# 01_Powersupply.net
KiCad netlist of a schematic drawn in Altium Designer
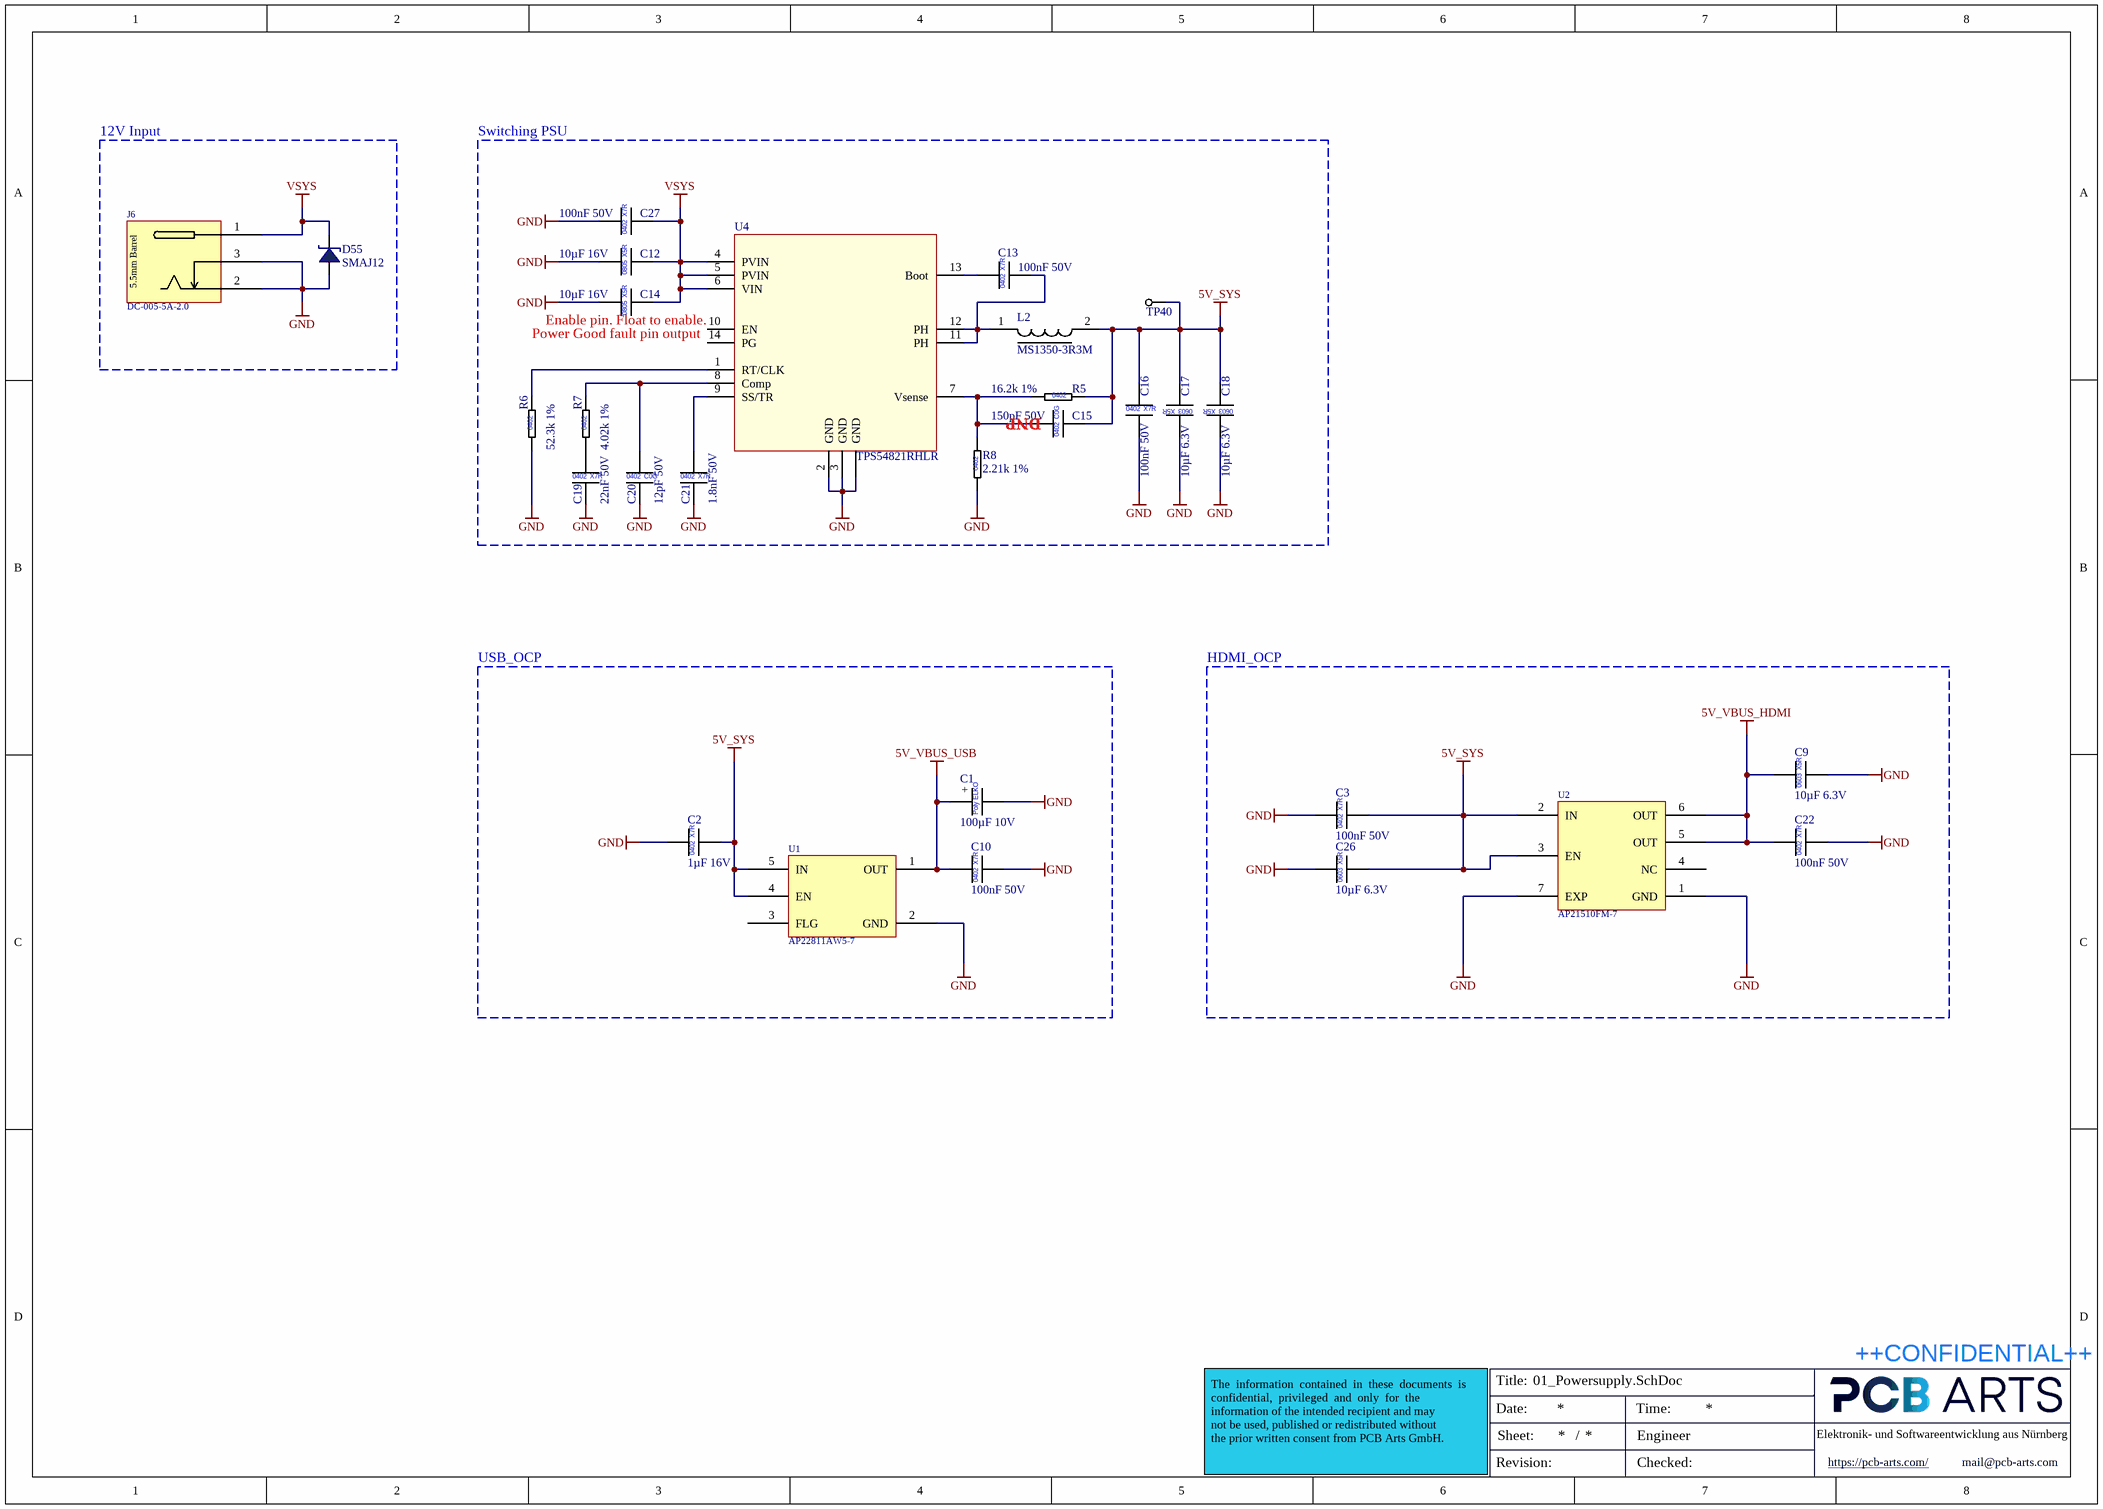
[diagram p0: 01_Powersupply.SchDoc]

(export (version "E")
  (design (tool "Eeschema 10.0.6"))
  (components
    (comp (ref "C1")
      (value "100µF 10V")
      (footprint "Cap:WCAP-ASLI_D5H5.5")
      (description "Organische Polymer-Aluminiumkondensatoren 100uF 10 Volts 20%")
      (libsource (lib "Cap") (part "CAP_D5L5.5_100µF_10V"))
    )
    (comp (ref "C2")
      (value "1µF 16V")
      (footprint "Cap:CAP_0402")
      (description "Multilayer Ceramic Capacitors MLCC - SMD/SMT 0402 16VDC")
      (libsource (lib "Cap") (part "CAP_0402_1µF_16V"))
    )
    (comp (ref "C3")
      (value "100nF 50V")
      (footprint "Cap:CAP_0402")
      (description "Multilayer Ceramic Capacitors MLCC - SMD/SMT 0402 50VDC")
      (libsource (lib "Cap") (part "CAP_0402_100nF_50V"))
    )
    (comp (ref "C9")
      (value "10µF 6.3V")
      (footprint "Cap:CAP_0603")
      (description "Multilayer Ceramic Capacitors MLCC - SMD/SMT 0603 6.3VDC")
      (libsource (lib "Cap") (part "CAP_0603_10µF_6.3V"))
    )
    (comp (ref "C10")
      (value "100nF 50V")
      (footprint "Cap:CAP_0402")
      (description "Multilayer Ceramic Capacitors MLCC - SMD/SMT 0402 50VDC")
      (libsource (lib "Cap") (part "CAP_0402_100nF_50V"))
    )
    (comp (ref "C12")
      (value "10µF 16V")
      (footprint "AlemNano 201029:CAP_0805")
      (description "Multilayer Ceramic Capacitors MLCC - SMD/SMT 0805 16VDC")
      (libsource (lib "AlemNano 201029") (part "CAP_0805_10µF_16V"))
    )
    (comp (ref "C13")
      (value "100nF 50V")
      (footprint "AlemNano 201029:CAP_0402")
      (description "Multilayer Ceramic Capacitors MLCC - SMD/SMT 0402 50VDC")
      (libsource (lib "AlemNano 201029") (part "CAP_0402_100nF_50V"))
    )
    (comp (ref "C14")
      (value "10µF 16V")
      (footprint "AlemNano 201029:CAP_0805")
      (description "Multilayer Ceramic Capacitors MLCC - SMD/SMT 0805 16VDC")
      (libsource (lib "AlemNano 201029") (part "CAP_0805_10µF_16V"))
    )
    (comp (ref "C15")
      (value "150pF 50V")
      (footprint "AlemNano 201029:CAP_0402")
      (description "Multilayer Ceramic Capacitors MLCC - SMD/SMT 0402 50VDC")
      (libsource (lib "AlemNano 201029") (part "CAP_0402_150pF_50V"))
    )
    (comp (ref "C16")
      (value "100nF 50V")
      (footprint "AlemNano 201029:CAP_0402")
      (description "Multilayer Ceramic Capacitors MLCC - SMD/SMT 0402 50VDC")
      (libsource (lib "") (part "CAP_0402_100nF_50V_1"))
    )
    (comp (ref "C17")
      (value "10µF 6.3V")
      (footprint "AlemNano 201029:CAP_0603")
      (description "Multilayer Ceramic Capacitors MLCC - SMD/SMT 0603 6.3VDC")
      (libsource (lib "AlemNano 201029") (part "CAP_0603_10µF_6.3V"))
    )
    (comp (ref "C18")
      (value "10µF 6.3V")
      (footprint "AlemNano 201029:CAP_0603")
      (description "Multilayer Ceramic Capacitors MLCC - SMD/SMT 0603 6.3VDC")
      (libsource (lib "AlemNano 201029") (part "CAP_0603_10µF_6.3V"))
    )
    (comp (ref "C19")
      (value "22nF 50V")
      (footprint "AlemNano 201029:CAP_0402")
      (description "Multilayer Ceramic Capacitors MLCC - SMD/SMT 0402 50VDC")
      (libsource (lib "AlemNano 201029") (part "CAP_0402_22nF_50V"))
    )
    (comp (ref "C20")
      (value "12pF 50V")
      (footprint "AlemNano 201029:CAP_0402")
      (description "Multilayer Ceramic Capacitors MLCC - SMD/SMT 0402 50VDC")
      (libsource (lib "AlemNano 201029") (part "CAP_0402_12pF_50V"))
    )
    (comp (ref "C21")
      (value "1.8nF 50V")
      (footprint "AlemNano 201029:CAP_0402")
      (description "Multilayer Ceramic Capacitors MLCC - SMD/SMT 0402 50VDC")
      (libsource (lib "AlemNano 201029") (part "CAP_0402_1.8nF_50V"))
    )
    (comp (ref "C22")
      (value "100nF 50V")
      (footprint "Cap:CAP_0402")
      (description "Multilayer Ceramic Capacitors MLCC - SMD/SMT 0402 50VDC")
      (libsource (lib "Cap") (part "CAP_0402_100nF_50V"))
    )
    (comp (ref "C26")
      (value "10µF 6.3V")
      (footprint "Cap:CAP_0603")
      (description "Multilayer Ceramic Capacitors MLCC - SMD/SMT 0603 6.3VDC")
      (libsource (lib "Cap") (part "CAP_0603_10µF_6.3V"))
    )
    (comp (ref "C27")
      (value "100nF 50V")
      (footprint "AlemNano 201029:CAP_0402")
      (description "Multilayer Ceramic Capacitors MLCC - SMD/SMT 0402 50VDC")
      (libsource (lib "AlemNano 201029") (part "CAP_0402_100nF_50V"))
    )
    (comp (ref "D55")
      (value "SMAJ12")
      (footprint "Protec:DO214AC")
      (description "TVS Diode, 12V, Unidirectional")
      (libsource (lib "Protec") (part "SMAJ12_TVS Diode, 12V, Unidirectional"))
    )
    (comp (ref "J6")
      (value "DC-005-5A-2.0")
      (footprint "Conn:DC-005-5A-2.0")
      (description "DC Power Receptacle Jack 5.5/2.1mm")
      (libsource (lib "Conn") (part "DC-005-5A-2.0_DC Power Receptacle Jack 5.5/2.1mm"))
    )
    (comp (ref "L2")
      (value "MS1350-3R3M")
      (footprint "AlemNano 201029:MS1350")
      (description "3.3uH ±20% 13A 7.5mΩ SMD,13.8x12.6x5mm Inductor")
      (libsource (lib "AlemNano 201029") (part "MS1350-3R3M  _3.3uH ±20% 13A 7.5mΩ SMD,13.8x12.6x5mm Inductor"))
    )
    (comp (ref "R5")
      (value "16.2k 1%")
      (footprint "AlemNano 201029:RES_0402")
      (description "Thick Film Resistors - SMD 16.2kOhm 1%")
      (libsource (lib "AlemNano 201029") (part "RES_0402_16.2k_1%"))
    )
    (comp (ref "R6")
      (value "52.3k 1%")
      (footprint "AlemNano 201029:RES_0402")
      (description "Thick Film Resistors - SMD 52.3kOhm 1%")
      (libsource (lib "AlemNano 201029") (part "RES_0402_52.3k_1%"))
    )
    (comp (ref "R7")
      (value "4.02k 1%")
      (footprint "AlemNano 201029:RES_0402")
      (description "Thick Film Resistors - SMD 4.02kOhm 1%")
      (libsource (lib "AlemNano 201029") (part "RES_0402_4.02k_1%"))
    )
    (comp (ref "R8")
      (value "2.21k 1%")
      (footprint "AlemNano 201029:RES_0402")
      (description "Thick Film Resistors - SMD 2.21kOhm 1%")
      (libsource (lib "AlemNano 201029") (part "RES_0402_2.21k_1%"))
    )
    (comp (ref "TP40")
      (value "Testpoint")
      (footprint "AlemNano 201029:Testpoint 0.8mm")
      (description "Testpoint 0.8mm")
      (libsource (lib "AlemNano 201029") (part "Testpoint 0.8mm"))
    )
    (comp (ref "U1")
      (value "AP22811AW5-7")
      (footprint "Power:SOT95P285X140-5N")
      (description "Power Switch ICs - Power Distribution Load Switch")
      (libsource (lib "Power") (part "AP22811AW5-7_Power Switch ICs - Power Distribution Load Switch"))
    )
    (comp (ref "U2")
      (value "AP21510FM-7")
      (footprint "Power:QFN50P201X181X60_HS-7N")
      (description "Power Switch ICs - Power Distribution 0.5A SGL Ch USB 2.0 Curr Limited Switch")
      (libsource (lib "Power") (part "AP21510FM-7_Power Switch ICs - Power Distribution Load Switch"))
    )
    (comp (ref "U4")
      (value "TPS54821RHLR")
      (footprint "AlemNano 201029:VQFN14U3535")
      (description "4.5 V to 17 V Input, 8 A Synchronous Step Down Converter")
      (libsource (lib "AlemNano 201029") (part "TPS54821RHLR_4.5 V to 17 V Input, 8 A Synchronous Step Down Converter"))
    )
  )
  (nets
    (net (code "1") (name "5V_SYS") (class "Default")
      (node (ref "C15") (pin "2") (pinfunction "2_2") (pintype "passive"))
      (node (ref "C16") (pin "1") (pinfunction "1_1") (pintype "passive"))
      (node (ref "C17") (pin "2") (pinfunction "2_2") (pintype "passive"))
      (node (ref "C18") (pin "2") (pinfunction "2_2") (pintype "passive"))
      (node (ref "C2") (pin "2") (pinfunction "2_2") (pintype "passive"))
      (node (ref "C26") (pin "2") (pinfunction "2_2") (pintype "passive"))
      (node (ref "C3") (pin "2") (pinfunction "2_2") (pintype "passive"))
      (node (ref "L2") (pin "2") (pinfunction "2_2") (pintype "passive"))
      (node (ref "R5") (pin "2") (pinfunction "2_2") (pintype "passive"))
      (node (ref "TP40") (pin "1") (pinfunction "GND_1") (pintype "passive"))
      (node (ref "U1") (pin "4") (pinfunction "EN_4") (pintype "passive"))
      (node (ref "U1") (pin "5") (pinfunction "IN_5") (pintype "power_in"))
      (node (ref "U2") (pin "2") (pinfunction "IN_2") (pintype "power_in"))
      (node (ref "U2") (pin "3") (pinfunction "EN_3") (pintype "power_in"))
    )
    (net (code "2") (name "5V_VBUS_HDMI") (class "Default")
      (node (ref "C22") (pin "1") (pinfunction "1_1") (pintype "passive"))
      (node (ref "C9") (pin "1") (pinfunction "1_1") (pintype "passive"))
      (node (ref "U2") (pin "5") (pinfunction "OUT_5") (pintype "power_in"))
      (node (ref "U2") (pin "6") (pinfunction "OUT_6") (pintype "power_in"))
    )
    (net (code "3") (name "5V_VBUS_USB") (class "Default")
      (node (ref "C1") (pin "1") (pinfunction "1_1") (pintype "passive"))
      (node (ref "C10") (pin "1") (pinfunction "1_1") (pintype "passive"))
      (node (ref "U1") (pin "1") (pinfunction "OUT_1") (pintype "power_in"))
    )
    (net (code "4") (name "GND") (class "Default")
      (node (ref "C1") (pin "2") (pinfunction "2_2") (pintype "passive"))
      (node (ref "C10") (pin "2") (pinfunction "2_2") (pintype "passive"))
      (node (ref "C12") (pin "1") (pinfunction "1_1") (pintype "passive"))
      (node (ref "C14") (pin "1") (pinfunction "1_1") (pintype "passive"))
      (node (ref "C16") (pin "2") (pinfunction "2_2") (pintype "passive"))
      (node (ref "C17") (pin "1") (pinfunction "1_1") (pintype "passive"))
      (node (ref "C18") (pin "1") (pinfunction "1_1") (pintype "passive"))
      (node (ref "C19") (pin "2") (pinfunction "2_2") (pintype "passive"))
      (node (ref "C2") (pin "1") (pinfunction "1_1") (pintype "passive"))
      (node (ref "C20") (pin "2") (pinfunction "2_2") (pintype "passive"))
      (node (ref "C21") (pin "2") (pinfunction "2_2") (pintype "passive"))
      (node (ref "C22") (pin "2") (pinfunction "2_2") (pintype "passive"))
      (node (ref "C26") (pin "1") (pinfunction "1_1") (pintype "passive"))
      (node (ref "C27") (pin "1") (pinfunction "1_1") (pintype "passive"))
      (node (ref "C3") (pin "1") (pinfunction "1_1") (pintype "passive"))
      (node (ref "C9") (pin "2") (pinfunction "2_2") (pintype "passive"))
      (node (ref "D55") (pin "2") (pinfunction "2_2") (pintype "passive"))
      (node (ref "J6") (pin "2") (pinfunction "2_2") (pintype "passive"))
      (node (ref "J6") (pin "3") (pinfunction "3_3") (pintype "passive"))
      (node (ref "R6") (pin "1") (pinfunction "1_1") (pintype "passive"))
      (node (ref "R8") (pin "1") (pinfunction "1_1") (pintype "passive"))
      (node (ref "U1") (pin "2") (pinfunction "GND_2") (pintype "power_in"))
      (node (ref "U2") (pin "1") (pinfunction "GND_1") (pintype "power_in"))
      (node (ref "U2") (pin "7") (pinfunction "EXP_7") (pintype "power_in"))
      (node (ref "U4") (pin "2") (pinfunction "GND_2") (pintype "passive"))
      (node (ref "U4") (pin "3") (pinfunction "GND_3") (pintype "passive"))
      (node (ref "U4") (pin "EXP") (pinfunction "GND_EXP") (pintype "passive"))
    )
    (net (code "5") (name "Net-(C13-Pad2)") (class "Default")
      (node (ref "C13") (pin "2") (pinfunction "2_2") (pintype "passive"))
      (node (ref "L2") (pin "1") (pinfunction "1_1") (pintype "passive"))
      (node (ref "U4") (pin "11") (pinfunction "PH_11") (pintype "passive"))
      (node (ref "U4") (pin "12") (pinfunction "PH_12") (pintype "passive"))
    )
    (net (code "6") (name "Net-(C19-Pad1)") (class "Default")
      (node (ref "C19") (pin "1") (pinfunction "1_1") (pintype "passive"))
      (node (ref "R7") (pin "1") (pinfunction "1_1") (pintype "passive"))
    )
    (net (code "7") (name "Net-(U4-Boot)") (class "Default")
      (node (ref "C13") (pin "1") (pinfunction "1_1") (pintype "passive"))
      (node (ref "U4") (pin "13") (pinfunction "Boot_13") (pintype "passive"))
    )
    (net (code "8") (name "Net-(U4-Comp)") (class "Default")
      (node (ref "C20") (pin "1") (pinfunction "1_1") (pintype "passive"))
      (node (ref "R7") (pin "2") (pinfunction "2_2") (pintype "passive"))
      (node (ref "U4") (pin "8") (pinfunction "Comp_8") (pintype "passive"))
    )
    (net (code "9") (name "Net-(U4-RT{slash}CLK)") (class "Default")
      (node (ref "R6") (pin "2") (pinfunction "2_2") (pintype "passive"))
      (node (ref "U4") (pin "1") (pinfunction "RT/CLK_1") (pintype "passive"))
    )
    (net (code "10") (name "Net-(U4-SS{slash}TR)") (class "Default")
      (node (ref "C21") (pin "1") (pinfunction "1_1") (pintype "passive"))
      (node (ref "U4") (pin "9") (pinfunction "SS/TR_9") (pintype "passive"))
    )
    (net (code "11") (name "Net-(U4-Vsense)") (class "Default")
      (node (ref "C15") (pin "1") (pinfunction "1_1") (pintype "passive"))
      (node (ref "R5") (pin "1") (pinfunction "1_1") (pintype "passive"))
      (node (ref "R8") (pin "2") (pinfunction "2_2") (pintype "passive"))
      (node (ref "U4") (pin "7") (pinfunction "Vsense_7") (pintype "passive"))
    )
    (net (code "12") (name "VSYS") (class "Default")
      (node (ref "C12") (pin "2") (pinfunction "2_2") (pintype "passive"))
      (node (ref "C14") (pin "2") (pinfunction "2_2") (pintype "passive"))
      (node (ref "C27") (pin "2") (pinfunction "2_2") (pintype "passive"))
      (node (ref "D55") (pin "1") (pinfunction "1_1") (pintype "passive"))
      (node (ref "J6") (pin "1") (pinfunction "1_1") (pintype "passive"))
      (node (ref "U4") (pin "4") (pinfunction "PVIN_4") (pintype "passive"))
      (node (ref "U4") (pin "5") (pinfunction "PVIN_5") (pintype "passive"))
      (node (ref "U4") (pin "6") (pinfunction "VIN_6") (pintype "passive"))
    )
    (net (code "13") (name "unconnected-(U1-FLG-Pad3)") (class "Default")
      (node (ref "U1") (pin "3") (pinfunction "FLG_3") (pintype "open_collector"))
    )
    (net (code "14") (name "unconnected-(U2-NC-Pad4)") (class "Default")
      (node (ref "U2") (pin "4") (pinfunction "NC_4") (pintype "power_in"))
    )
    (net (code "15") (name "unconnected-(U4-EN-Pad10)") (class "Default")
      (node (ref "U4") (pin "10") (pinfunction "EN_10") (pintype "passive"))
    )
    (net (code "16") (name "unconnected-(U4-PG-Pad14)") (class "Default")
      (node (ref "U4") (pin "14") (pinfunction "PG_14") (pintype "passive"))
    )
  )
)
